# Copy_of_RoverBreakout2.net
KiCad netlist of a schematic drawn in Altium Designer
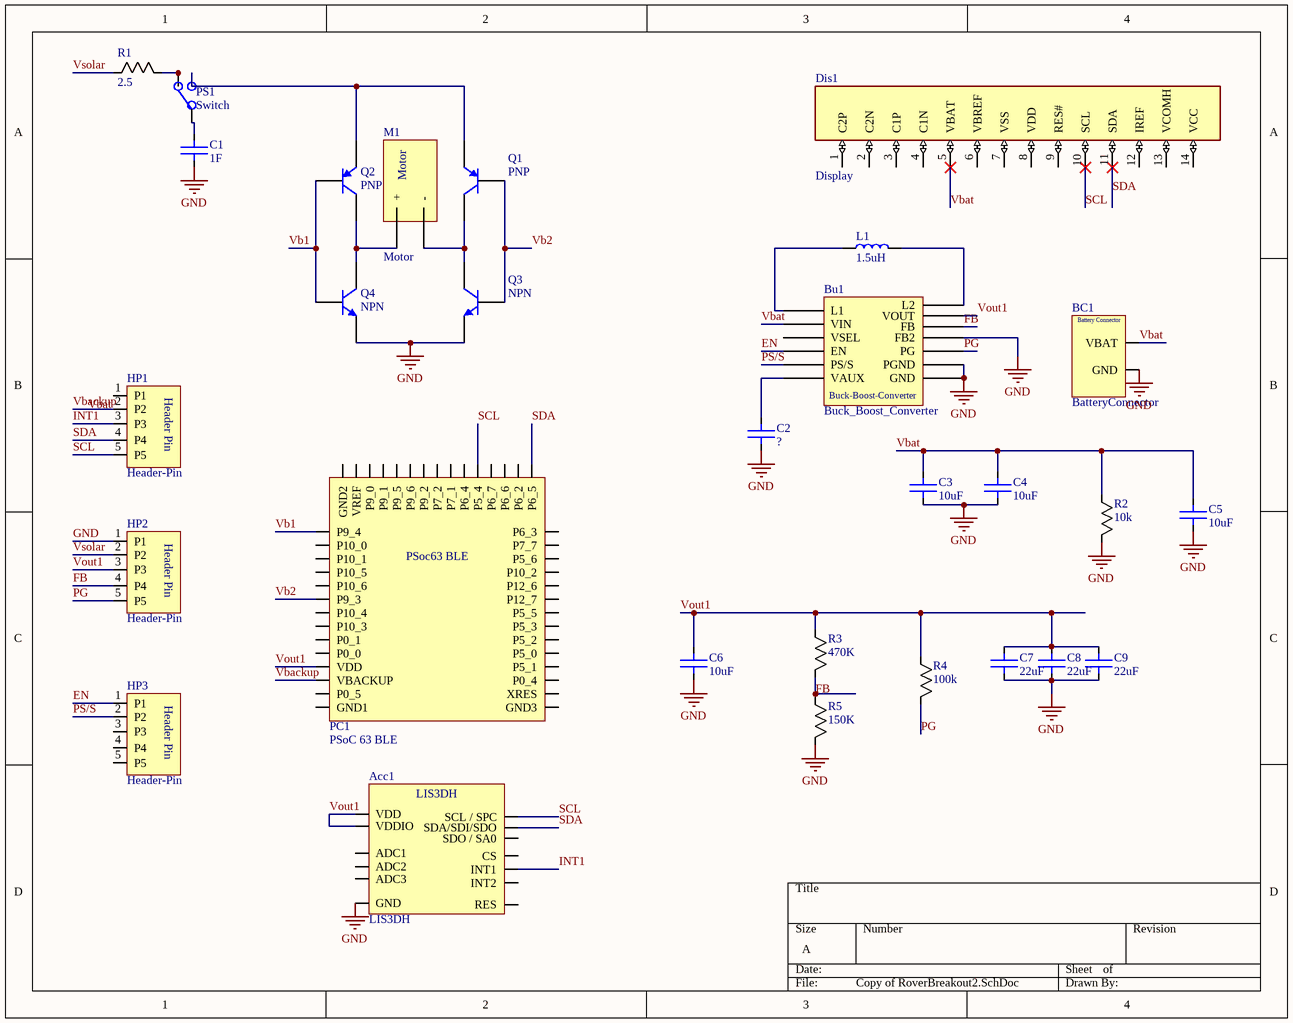
[diagram p0: Copy of RoverBreakout2.SchDoc]

(export (version "E")
  (design (tool "Eeschema 10.0.6"))
  (components
    (comp (ref "Acc1") (value "LIS3DH") (footprint "LIS3DH") (libsource (lib "SeniorDesign") (part "LIS3DH")))
    (comp (ref "BC1")
      (value "BatteryConnector")
      (footprint "BatteryConnector")
      (libsource (lib "SeniorDesign") (part "BatteryConnector"))
    )
    (comp (ref "Bu1")
      (value "Buck_Boost_Converter")
      (footprint "Buck_Boost_Converter")
      (libsource (lib "ISeniorDesign") (part "Buck_Boost_Converter"))
    )
    (comp (ref "C1")
      (value "1F")
      (footprint "PASSIVE-CAPACITOR-0603")
      (fields (field (name "Comment") "Capacitor1"))
      (libsource (lib "ISeniorDesign") (part "Capacitor1"))
    )
    (comp (ref "C2")
      (value "?")
      (footprint "PASSIVE-CAPACITOR-0603")
      (fields (field (name "Comment") "Capacitor1"))
      (libsource (lib "ISeniorDesign") (part "Capacitor1"))
    )
    (comp (ref "C3")
      (value "10uF")
      (footprint "PASSIVE-CAPACITOR-0603")
      (fields (field (name "Comment") "Capacitor1"))
      (libsource (lib "ISeniorDesign") (part "Capacitor1"))
    )
    (comp (ref "C4")
      (value "10uF")
      (footprint "PASSIVE-CAPACITOR-0603")
      (fields (field (name "Comment") "Capacitor1"))
      (libsource (lib "ISeniorDesign") (part "Capacitor1"))
    )
    (comp (ref "C5")
      (value "10uF")
      (footprint "PASSIVE-CAPACITOR-0603")
      (fields (field (name "Comment") "Capacitor1"))
      (libsource (lib "ISeniorDesign") (part "Capacitor1"))
    )
    (comp (ref "C6")
      (value "10uF")
      (footprint "PASSIVE-CAPACITOR-0603")
      (fields (field (name "Comment") "Capacitor1"))
      (libsource (lib "ISeniorDesign") (part "Capacitor1"))
    )
    (comp (ref "C7")
      (value "22uF")
      (footprint "PASSIVE-CAPACITOR-0603")
      (fields (field (name "Comment") "Capacitor1"))
      (libsource (lib "ISeniorDesign") (part "Capacitor1"))
    )
    (comp (ref "C8")
      (value "22uF")
      (footprint "PASSIVE-CAPACITOR-0603")
      (fields (field (name "Comment") "Capacitor1"))
      (libsource (lib "ISeniorDesign") (part "Capacitor1"))
    )
    (comp (ref "C9")
      (value "22uF")
      (footprint "PASSIVE-CAPACITOR-0603")
      (fields (field (name "Comment") "Capacitor1"))
      (libsource (lib "ISeniorDesign") (part "Capacitor1"))
    )
    (comp (ref "Dis1")
      (value "Display")
      (footprint "Display")
      (libsource (lib "SeniorDesign") (part "Display"))
    )
    (comp (ref "HP1")
      (value "Header-Pin")
      (footprint "Header_Pin")
      (libsource (lib "SeniorDesign") (part "Header-Pin"))
    )
    (comp (ref "HP2")
      (value "Header-Pin")
      (footprint "Header_Pin")
      (libsource (lib "SeniorDesign") (part "Header-Pin"))
    )
    (comp (ref "HP3")
      (value "Header-Pin")
      (footprint "Header_Pin")
      (libsource (lib "SeniorDesign") (part "Header-Pin"))
    )
    (comp (ref "L1")
      (value "1.5uH")
      (footprint "PASSIVE-INDUCTOR-0603")
      (fields (field (name "Comment") "Inductor"))
      (libsource (lib "ISeniorDesign") (part "Inductor"))
    )
    (comp (ref "M1") (value "Motor") (footprint "Motor") (libsource (lib "ISeniorDesign") (part "Motor")))
    (comp (ref "PC1")
      (value "PSoC 63 BLE")
      (footprint "PSoC-63 BLE")
      (libsource (lib "ISeniorDesign") (part "PSoC 63 BLE"))
    )
    (comp (ref "PS1")
      (value "Switch")
      (footprint "3-Way Switch")
      (libsource (lib "SeniorDesign") (part "Switch"))
    )
    (comp (ref "Q1")
      (value "PNP")
      (footprint "SOT-23B_N")
      (description "PNP Bipolar Transistor")
      (fields (field (name "PUBLISHER") "Altium Limited"))
      (libsource (lib "Miscellaneous Devices") (part "PNP"))
    )
    (comp (ref "Q2")
      (value "PNP")
      (footprint "SOT-23B_N")
      (description "PNP Bipolar Transistor")
      (fields (field (name "PUBLISHER") "Altium Limited"))
      (libsource (lib "Miscellaneous Devices") (part "PNP"))
    )
    (comp (ref "Q3")
      (value "NPN")
      (footprint "TO-226-AA")
      (description "NPN Bipolar Transistor")
      (fields (field (name "PUBLISHER") "Altium Limited"))
      (libsource (lib "Miscellaneous Devices") (part "NPN"))
    )
    (comp (ref "Q4")
      (value "NPN")
      (footprint "TO-226-AA")
      (description "NPN Bipolar Transistor")
      (fields (field (name "PUBLISHER") "Altium Limited"))
      (libsource (lib "Miscellaneous Devices") (part "NPN"))
    )
    (comp (ref "R1")
      (value "2.5")
      (footprint "PASSIVE-RESISTOR-0603")
      (fields (field (name "Comment") "Resistor"))
      (libsource (lib "ISeniorDesign") (part "Resistor1"))
    )
    (comp (ref "R2")
      (value "10k")
      (footprint "PASSIVE-RESISTOR-0603")
      (fields (field (name "Comment") "Resistor"))
      (libsource (lib "ISeniorDesign") (part "Resistor1"))
    )
    (comp (ref "R3")
      (value "470K")
      (footprint "PASSIVE-RESISTOR-0603")
      (fields (field (name "Comment") "Resistor"))
      (libsource (lib "ISeniorDesign") (part "Resistor1"))
    )
    (comp (ref "R4")
      (value "100k")
      (footprint "PASSIVE-RESISTOR-0603")
      (fields (field (name "Comment") "Resistor"))
      (libsource (lib "ISeniorDesign") (part "Resistor1"))
    )
    (comp (ref "R5")
      (value "150K")
      (footprint "PASSIVE-RESISTOR-0603")
      (fields (field (name "Comment") "Resistor"))
      (libsource (lib "ISeniorDesign") (part "Resistor1"))
    )
  )
  (nets
    (net (code "1") (name "/EN") (class "Default")
      (node (ref "Bu1") (pin "EN") (pinfunction "EN_EN") (pintype "passive"))
      (node (ref "HP3") (pin "1") (pinfunction "P1_1") (pintype "passive"))
    )
    (net (code "2") (name "/FB") (class "Default")
      (node (ref "Bu1") (pin "FB") (pinfunction "FB_FB") (pintype "passive"))
      (node (ref "HP2") (pin "4") (pinfunction "P4_4") (pintype "passive"))
      (node (ref "R3") (pin "2") (pinfunction "2_2") (pintype "passive"))
      (node (ref "R5") (pin "1") (pinfunction "1_1") (pintype "passive"))
    )
    (net (code "3") (name "/INT1") (class "Default")
      (node (ref "Acc1") (pin "INT1") (pinfunction "INT1_INT1") (pintype "passive"))
      (node (ref "HP1") (pin "3") (pinfunction "P3_3") (pintype "passive"))
    )
    (net (code "4") (name "/PG") (class "Default")
      (node (ref "Bu1") (pin "PG") (pinfunction "PG_PG") (pintype "passive"))
      (node (ref "HP2") (pin "5") (pinfunction "P5_5") (pintype "passive"))
      (node (ref "R4") (pin "2") (pinfunction "2_2") (pintype "passive"))
    )
    (net (code "5") (name "/PS{slash}S") (class "Default")
      (node (ref "Bu1") (pin "PS/S") (pinfunction "PS/S_PS/S") (pintype "passive"))
      (node (ref "HP3") (pin "2") (pinfunction "P2_2") (pintype "passive"))
    )
    (net (code "6") (name "/SCL") (class "Default")
      (node (ref "Acc1") (pin "SCL_/_SPC") (pinfunction "SCL_/_SPC_SCL_/_SPC") (pintype "passive"))
      (node (ref "Dis1") (pin "10") (pinfunction "SCL_10") (pintype "bidirectional"))
      (node (ref "HP1") (pin "5") (pinfunction "P5_5") (pintype "passive"))
      (node (ref "PC1") (pin "25") (pinfunction "P5_4_25") (pintype "passive"))
    )
    (net (code "7") (name "/SDA") (class "Default")
      (node (ref "Acc1") (pin "SDA/SDI/SDO") (pinfunction "SDA/SDI/SDO_SDA/SDI/SDO") (pintype "passive"))
      (node (ref "Dis1") (pin "11") (pinfunction "SDA_11") (pintype "bidirectional"))
      (node (ref "HP1") (pin "4") (pinfunction "P4_4") (pintype "passive"))
      (node (ref "PC1") (pin "29") (pinfunction "P6_5_29") (pintype "passive"))
    )
    (net (code "8") (name "/Vb1") (class "Default")
      (node (ref "PC1") (pin "14") (pinfunction "P9_4_14") (pintype "passive"))
      (node (ref "Q2") (pin "2") (pinfunction "B_2") (pintype "passive"))
      (node (ref "Q4") (pin "2") (pinfunction "B_2") (pintype "passive"))
    )
    (net (code "9") (name "/Vb2") (class "Default")
      (node (ref "PC1") (pin "9") (pinfunction "P9_3_9") (pintype "passive"))
      (node (ref "Q1") (pin "2") (pinfunction "B_2") (pintype "passive"))
      (node (ref "Q3") (pin "2") (pinfunction "B_2") (pintype "passive"))
    )
    (net (code "10") (name "/Vbackup") (class "Default")
      (node (ref "HP1") (pin "2") (pinfunction "P2_2") (pintype "passive"))
      (node (ref "PC1") (pin "3") (pinfunction "VBACKUP_3") (pintype "passive"))
    )
    (net (code "11") (name "/Vbat") (class "Default")
      (node (ref "BC1") (pin "VBAT") (pinfunction "VBAT_VBAT") (pintype "passive"))
      (node (ref "Bu1") (pin "VIN") (pinfunction "VIN_VIN") (pintype "passive"))
      (node (ref "C3") (pin "2") (pinfunction "2_2") (pintype "passive"))
      (node (ref "C4") (pin "2") (pinfunction "2_2") (pintype "passive"))
      (node (ref "C5") (pin "2") (pinfunction "2_2") (pintype "passive"))
      (node (ref "Dis1") (pin "5") (pinfunction "VBAT_5") (pintype "bidirectional"))
      (node (ref "HP1") (pin "1") (pinfunction "P1_1") (pintype "passive"))
      (node (ref "R2") (pin "1") (pinfunction "1_1") (pintype "passive"))
    )
    (net (code "12") (name "/Vout1") (class "Default")
      (node (ref "Acc1") (pin "VDD") (pinfunction "VDD_VDD") (pintype "passive"))
      (node (ref "Acc1") (pin "VDDIO") (pinfunction "VDDIO_VDDIO") (pintype "passive"))
      (node (ref "Bu1") (pin "VOUT") (pinfunction "VOUT_VOUT") (pintype "passive"))
      (node (ref "C6") (pin "2") (pinfunction "2_2") (pintype "passive"))
      (node (ref "C7") (pin "2") (pinfunction "2_2") (pintype "passive"))
      (node (ref "C8") (pin "2") (pinfunction "2_2") (pintype "passive"))
      (node (ref "C9") (pin "2") (pinfunction "2_2") (pintype "passive"))
      (node (ref "HP2") (pin "3") (pinfunction "P3_3") (pintype "passive"))
      (node (ref "PC1") (pin "4") (pinfunction "VDD_4") (pintype "passive"))
      (node (ref "R3") (pin "1") (pinfunction "1_1") (pintype "passive"))
      (node (ref "R4") (pin "1") (pinfunction "1_1") (pintype "passive"))
    )
    (net (code "13") (name "/Vsolar") (class "Default")
      (node (ref "HP2") (pin "2") (pinfunction "P2_2") (pintype "passive"))
      (node (ref "R1") (pin "1") (pinfunction "1_1") (pintype "passive"))
    )
    (net (code "14") (name "GND") (class "Default")
      (node (ref "Acc1") (pin "GND") (pinfunction "GND_GND") (pintype "passive"))
      (node (ref "BC1") (pin "GND") (pinfunction "GND_GND") (pintype "passive"))
      (node (ref "Bu1") (pin "FB2") (pinfunction "FB2_FB2") (pintype "passive"))
      (node (ref "Bu1") (pin "GND") (pinfunction "GND_GND") (pintype "passive"))
      (node (ref "Bu1") (pin "PGND") (pinfunction "PGND_PGND") (pintype "passive"))
      (node (ref "C1") (pin "1") (pinfunction "1_1") (pintype "passive"))
      (node (ref "C2") (pin "1") (pinfunction "1_1") (pintype "passive"))
      (node (ref "C3") (pin "1") (pinfunction "1_1") (pintype "passive"))
      (node (ref "C4") (pin "1") (pinfunction "1_1") (pintype "passive"))
      (node (ref "C5") (pin "1") (pinfunction "1_1") (pintype "passive"))
      (node (ref "C6") (pin "1") (pinfunction "1_1") (pintype "passive"))
      (node (ref "C7") (pin "1") (pinfunction "1_1") (pintype "passive"))
      (node (ref "C8") (pin "1") (pinfunction "1_1") (pintype "passive"))
      (node (ref "C9") (pin "1") (pinfunction "1_1") (pintype "passive"))
      (node (ref "HP2") (pin "1") (pinfunction "P1_1") (pintype "passive"))
      (node (ref "Q3") (pin "3") (pinfunction "E_3") (pintype "passive"))
      (node (ref "Q4") (pin "3") (pinfunction "E_3") (pintype "passive"))
      (node (ref "R2") (pin "2") (pinfunction "2_2") (pintype "passive"))
      (node (ref "R5") (pin "2") (pinfunction "2_2") (pintype "passive"))
    )
    (net (code "15") (name "Net-(Bu1-PadL1)") (class "Default")
      (node (ref "Bu1") (pin "L1") (pinfunction "L1_L1") (pintype "passive"))
      (node (ref "L1") (pin "1") (pinfunction "1_1") (pintype "passive"))
    )
    (net (code "16") (name "Net-(Bu1-PadL2)") (class "Default")
      (node (ref "Bu1") (pin "L2") (pinfunction "L2_L2") (pintype "passive"))
      (node (ref "L1") (pin "2") (pinfunction "2_2") (pintype "passive"))
    )
    (net (code "17") (name "Net-(Bu1-PadVAUX)") (class "Default")
      (node (ref "Bu1") (pin "VAUX") (pinfunction "VAUX_VAUX") (pintype "passive"))
      (node (ref "C2") (pin "2") (pinfunction "2_2") (pintype "passive"))
    )
    (net (code "18") (name "Net-(C1-Pad2)") (class "Default")
      (node (ref "C1") (pin "2") (pinfunction "2_2") (pintype "passive"))
      (node (ref "PS1") (pin "2") (pinfunction "2_2") (pintype "passive"))
    )
    (net (code "19") (name "Net-(M1-+)") (class "Default")
      (node (ref "M1") (pin "1") (pinfunction "+_1") (pintype "passive"))
      (node (ref "Q2") (pin "1") (pinfunction "C_1") (pintype "passive"))
      (node (ref "Q4") (pin "1") (pinfunction "C_1") (pintype "passive"))
    )
    (net (code "20") (name "Net-(M1--)") (class "Default")
      (node (ref "M1") (pin "2") (pinfunction "-_2") (pintype "passive"))
      (node (ref "Q1") (pin "1") (pinfunction "C_1") (pintype "passive"))
      (node (ref "Q3") (pin "1") (pinfunction "C_1") (pintype "passive"))
    )
    (net (code "21") (name "Net-(PS1-Pad1)") (class "Default")
      (node (ref "PS1") (pin "1") (pinfunction "1_1") (pintype "passive"))
      (node (ref "R1") (pin "2") (pinfunction "2_2") (pintype "passive"))
    )
    (net (code "22") (name "Net-(Q1-E)") (class "Default")
      (node (ref "PS1") (pin "3") (pinfunction "3_3") (pintype "passive"))
      (node (ref "Q1") (pin "3") (pinfunction "E_3") (pintype "passive"))
      (node (ref "Q2") (pin "3") (pinfunction "E_3") (pintype "passive"))
    )
    (net (code "23") (name "unconnected-(Acc1-PadADC1)") (class "Default")
      (node (ref "Acc1") (pin "ADC1") (pinfunction "ADC1_ADC1") (pintype "passive"))
    )
    (net (code "24") (name "unconnected-(Acc1-PadADC2)") (class "Default")
      (node (ref "Acc1") (pin "ADC2") (pinfunction "ADC2_ADC2") (pintype "passive"))
    )
    (net (code "25") (name "unconnected-(Acc1-PadADC3)") (class "Default")
      (node (ref "Acc1") (pin "ADC3") (pinfunction "ADC3_ADC3") (pintype "passive"))
    )
    (net (code "26") (name "unconnected-(Acc1-PadCS)") (class "Default")
      (node (ref "Acc1") (pin "CS") (pinfunction "CS_CS") (pintype "passive"))
    )
    (net (code "27") (name "unconnected-(Acc1-PadINT2)") (class "Default")
      (node (ref "Acc1") (pin "INT2") (pinfunction "INT2_INT2") (pintype "passive"))
    )
    (net (code "28") (name "unconnected-(Acc1-PadRES)") (class "Default")
      (node (ref "Acc1") (pin "RES") (pinfunction "RES_RES") (pintype "passive"))
    )
    (net (code "29") (name "unconnected-(Acc1-PadSDO_{slash}_SA0)") (class "Default")
      (node (ref "Acc1") (pin "SDO_/_SA0") (pinfunction "SDO_/_SA0_SDO_/_SA0") (pintype "passive"))
    )
    (net (code "30") (name "unconnected-(Bu1-PadVSEL)") (class "Default")
      (node (ref "Bu1") (pin "VSEL") (pinfunction "VSEL_VSEL") (pintype "passive"))
    )
    (net (code "31") (name "unconnected-(Dis1-C1N-Pad4)") (class "Default")
      (node (ref "Dis1") (pin "4") (pinfunction "C1N_4") (pintype "bidirectional"))
    )
    (net (code "32") (name "unconnected-(Dis1-C1P-Pad3)") (class "Default")
      (node (ref "Dis1") (pin "3") (pinfunction "C1P_3") (pintype "bidirectional"))
    )
    (net (code "33") (name "unconnected-(Dis1-C2N-Pad2)") (class "Default")
      (node (ref "Dis1") (pin "2") (pinfunction "C2N_2") (pintype "bidirectional"))
    )
    (net (code "34") (name "unconnected-(Dis1-C2P-Pad1)") (class "Default")
      (node (ref "Dis1") (pin "1") (pinfunction "C2P_1") (pintype "bidirectional"))
    )
    (net (code "35") (name "unconnected-(Dis1-IREF-Pad12)") (class "Default")
      (node (ref "Dis1") (pin "12") (pinfunction "IREF_12") (pintype "bidirectional"))
    )
    (net (code "36") (name "unconnected-(Dis1-RES#-Pad9)") (class "Default")
      (node (ref "Dis1") (pin "9") (pinfunction "RES#_9") (pintype "bidirectional"))
    )
    (net (code "37") (name "unconnected-(Dis1-VBREF-Pad6)") (class "Default")
      (node (ref "Dis1") (pin "6") (pinfunction "VBREF_6") (pintype "bidirectional"))
    )
    (net (code "38") (name "unconnected-(Dis1-VCC-Pad14)") (class "Default")
      (node (ref "Dis1") (pin "14") (pinfunction "VCC_14") (pintype "bidirectional"))
    )
    (net (code "39") (name "unconnected-(Dis1-VCOMH-Pad13)") (class "Default")
      (node (ref "Dis1") (pin "13") (pinfunction "VCOMH_13") (pintype "bidirectional"))
    )
    (net (code "40") (name "unconnected-(Dis1-VDD-Pad8)") (class "Default")
      (node (ref "Dis1") (pin "8") (pinfunction "VDD_8") (pintype "bidirectional"))
    )
    (net (code "41") (name "unconnected-(Dis1-VSS-Pad7)") (class "Default")
      (node (ref "Dis1") (pin "7") (pinfunction "VSS_7") (pintype "bidirectional"))
    )
    (net (code "42") (name "unconnected-(HP3-P3-Pad3)") (class "Default")
      (node (ref "HP3") (pin "3") (pinfunction "P3_3") (pintype "passive"))
    )
    (net (code "43") (name "unconnected-(HP3-P4-Pad4)") (class "Default")
      (node (ref "HP3") (pin "4") (pinfunction "P4_4") (pintype "passive"))
    )
    (net (code "44") (name "unconnected-(HP3-P5-Pad5)") (class "Default")
      (node (ref "HP3") (pin "5") (pinfunction "P5_5") (pintype "passive"))
    )
    (net (code "45") (name "unconnected-(PC1-GND1-Pad1)") (class "Default")
      (node (ref "PC1") (pin "1") (pinfunction "GND1_1") (pintype "passive"))
    )
    (net (code "46") (name "unconnected-(PC1-GND2-Pad15)") (class "Default")
      (node (ref "PC1") (pin "15") (pinfunction "GND2_15") (pintype "passive"))
    )
    (net (code "47") (name "unconnected-(PC1-GND3-Pad43)") (class "Default")
      (node (ref "PC1") (pin "43") (pinfunction "GND3_43") (pintype "passive"))
    )
    (net (code "48") (name "unconnected-(PC1-P0_0-Pad5)") (class "Default")
      (node (ref "PC1") (pin "5") (pinfunction "P0_0_5") (pintype "passive"))
    )
    (net (code "49") (name "unconnected-(PC1-P0_1-Pad6)") (class "Default")
      (node (ref "PC1") (pin "6") (pinfunction "P0_1_6") (pintype "passive"))
    )
    (net (code "50") (name "unconnected-(PC1-P0_4-Pad41)") (class "Default")
      (node (ref "PC1") (pin "41") (pinfunction "P0_4_41") (pintype "passive"))
    )
    (net (code "51") (name "unconnected-(PC1-P0_5-Pad2)") (class "Default")
      (node (ref "PC1") (pin "2") (pinfunction "P0_5_2") (pintype "passive"))
    )
    (net (code "52") (name "unconnected-(PC1-P5_0-Pad39)") (class "Default")
      (node (ref "PC1") (pin "39") (pinfunction "P5_0_39") (pintype "passive"))
    )
    (net (code "53") (name "unconnected-(PC1-P5_1-Pad40)") (class "Default")
      (node (ref "PC1") (pin "40") (pinfunction "P5_1_40") (pintype "passive"))
    )
    (net (code "54") (name "unconnected-(PC1-P5_2-Pad38)") (class "Default")
      (node (ref "PC1") (pin "38") (pinfunction "P5_2_38") (pintype "passive"))
    )
    (net (code "55") (name "unconnected-(PC1-P5_3-Pad37)") (class "Default")
      (node (ref "PC1") (pin "37") (pinfunction "P5_3_37") (pintype "passive"))
    )
    (net (code "56") (name "unconnected-(PC1-P5_5-Pad36)") (class "Default")
      (node (ref "PC1") (pin "36") (pinfunction "P5_5_36") (pintype "passive"))
    )
    (net (code "57") (name "unconnected-(PC1-P5_6-Pad32)") (class "Default")
      (node (ref "PC1") (pin "32") (pinfunction "P5_6_32") (pintype "passive"))
    )
    (net (code "58") (name "unconnected-(PC1-P6_2-Pad28)") (class "Default")
      (node (ref "PC1") (pin "28") (pinfunction "P6_2_28") (pintype "passive"))
    )
    (net (code "59") (name "unconnected-(PC1-P6_3-Pad30)") (class "Default")
      (node (ref "PC1") (pin "30") (pinfunction "P6_3_30") (pintype "passive"))
    )
    (net (code "60") (name "unconnected-(PC1-P6_4-Pad24)") (class "Default")
      (node (ref "PC1") (pin "24") (pinfunction "P6_4_24") (pintype "passive"))
    )
    (net (code "61") (name "unconnected-(PC1-P6_6-Pad27)") (class "Default")
      (node (ref "PC1") (pin "27") (pinfunction "P6_6_27") (pintype "passive"))
    )
    (net (code "62") (name "unconnected-(PC1-P6_7-Pad26)") (class "Default")
      (node (ref "PC1") (pin "26") (pinfunction "P6_7_26") (pintype "passive"))
    )
    (net (code "63") (name "unconnected-(PC1-P7_1-Pad23)") (class "Default")
      (node (ref "PC1") (pin "23") (pinfunction "P7_1_23") (pintype "passive"))
    )
    (net (code "64") (name "unconnected-(PC1-P7_2-Pad22)") (class "Default")
      (node (ref "PC1") (pin "22") (pinfunction "P7_2_22") (pintype "passive"))
    )
    (net (code "65") (name "unconnected-(PC1-P7_7-Pad31)") (class "Default")
      (node (ref "PC1") (pin "31") (pinfunction "P7_7_31") (pintype "passive"))
    )
    (net (code "66") (name "unconnected-(PC1-P9_0-Pad17)") (class "Default")
      (node (ref "PC1") (pin "17") (pinfunction "P9_0_17") (pintype "passive"))
    )
    (net (code "67") (name "unconnected-(PC1-P9_1-Pad18)") (class "Default")
      (node (ref "PC1") (pin "18") (pinfunction "P9_1_18") (pintype "passive"))
    )
    (net (code "68") (name "unconnected-(PC1-P9_2-Pad21)") (class "Default")
      (node (ref "PC1") (pin "21") (pinfunction "P9_2_21") (pintype "passive"))
    )
    (net (code "69") (name "unconnected-(PC1-P9_5-Pad19)") (class "Default")
      (node (ref "PC1") (pin "19") (pinfunction "P9_5_19") (pintype "passive"))
    )
    (net (code "70") (name "unconnected-(PC1-P9_6-Pad20)") (class "Default")
      (node (ref "PC1") (pin "20") (pinfunction "P9_6_20") (pintype "passive"))
    )
    (net (code "71") (name "unconnected-(PC1-P10_0-Pad13)") (class "Default")
      (node (ref "PC1") (pin "13") (pinfunction "P10_0_13") (pintype "passive"))
    )
    (net (code "72") (name "unconnected-(PC1-P10_1-Pad12)") (class "Default")
      (node (ref "PC1") (pin "12") (pinfunction "P10_1_12") (pintype "passive"))
    )
    (net (code "73") (name "unconnected-(PC1-P10_2-Pad33)") (class "Default")
      (node (ref "PC1") (pin "33") (pinfunction "P10_2_33") (pintype "passive"))
    )
    (net (code "74") (name "unconnected-(PC1-P10_3-Pad7)") (class "Default")
      (node (ref "PC1") (pin "7") (pinfunction "P10_3_7") (pintype "passive"))
    )
    (net (code "75") (name "unconnected-(PC1-P10_4-Pad8)") (class "Default")
      (node (ref "PC1") (pin "8") (pinfunction "P10_4_8") (pintype "passive"))
    )
    (net (code "76") (name "unconnected-(PC1-P10_5-Pad11)") (class "Default")
      (node (ref "PC1") (pin "11") (pinfunction "P10_5_11") (pintype "passive"))
    )
    (net (code "77") (name "unconnected-(PC1-P10_6-Pad10)") (class "Default")
      (node (ref "PC1") (pin "10") (pinfunction "P10_6_10") (pintype "passive"))
    )
    (net (code "78") (name "unconnected-(PC1-P12_6-Pad34)") (class "Default")
      (node (ref "PC1") (pin "34") (pinfunction "P12_6_34") (pintype "passive"))
    )
    (net (code "79") (name "unconnected-(PC1-P12_7-Pad35)") (class "Default")
      (node (ref "PC1") (pin "35") (pinfunction "P12_7_35") (pintype "passive"))
    )
    (net (code "80") (name "unconnected-(PC1-VREF-Pad16)") (class "Default")
      (node (ref "PC1") (pin "16") (pinfunction "VREF_16") (pintype "passive"))
    )
    (net (code "81") (name "unconnected-(PC1-XRES-Pad42)") (class "Default")
      (node (ref "PC1") (pin "42") (pinfunction "XRES_42") (pintype "passive"))
    )
  )
)
